# Page07_CPU_PHY.net
KiCad netlist of a schematic drawn in Altium Designer
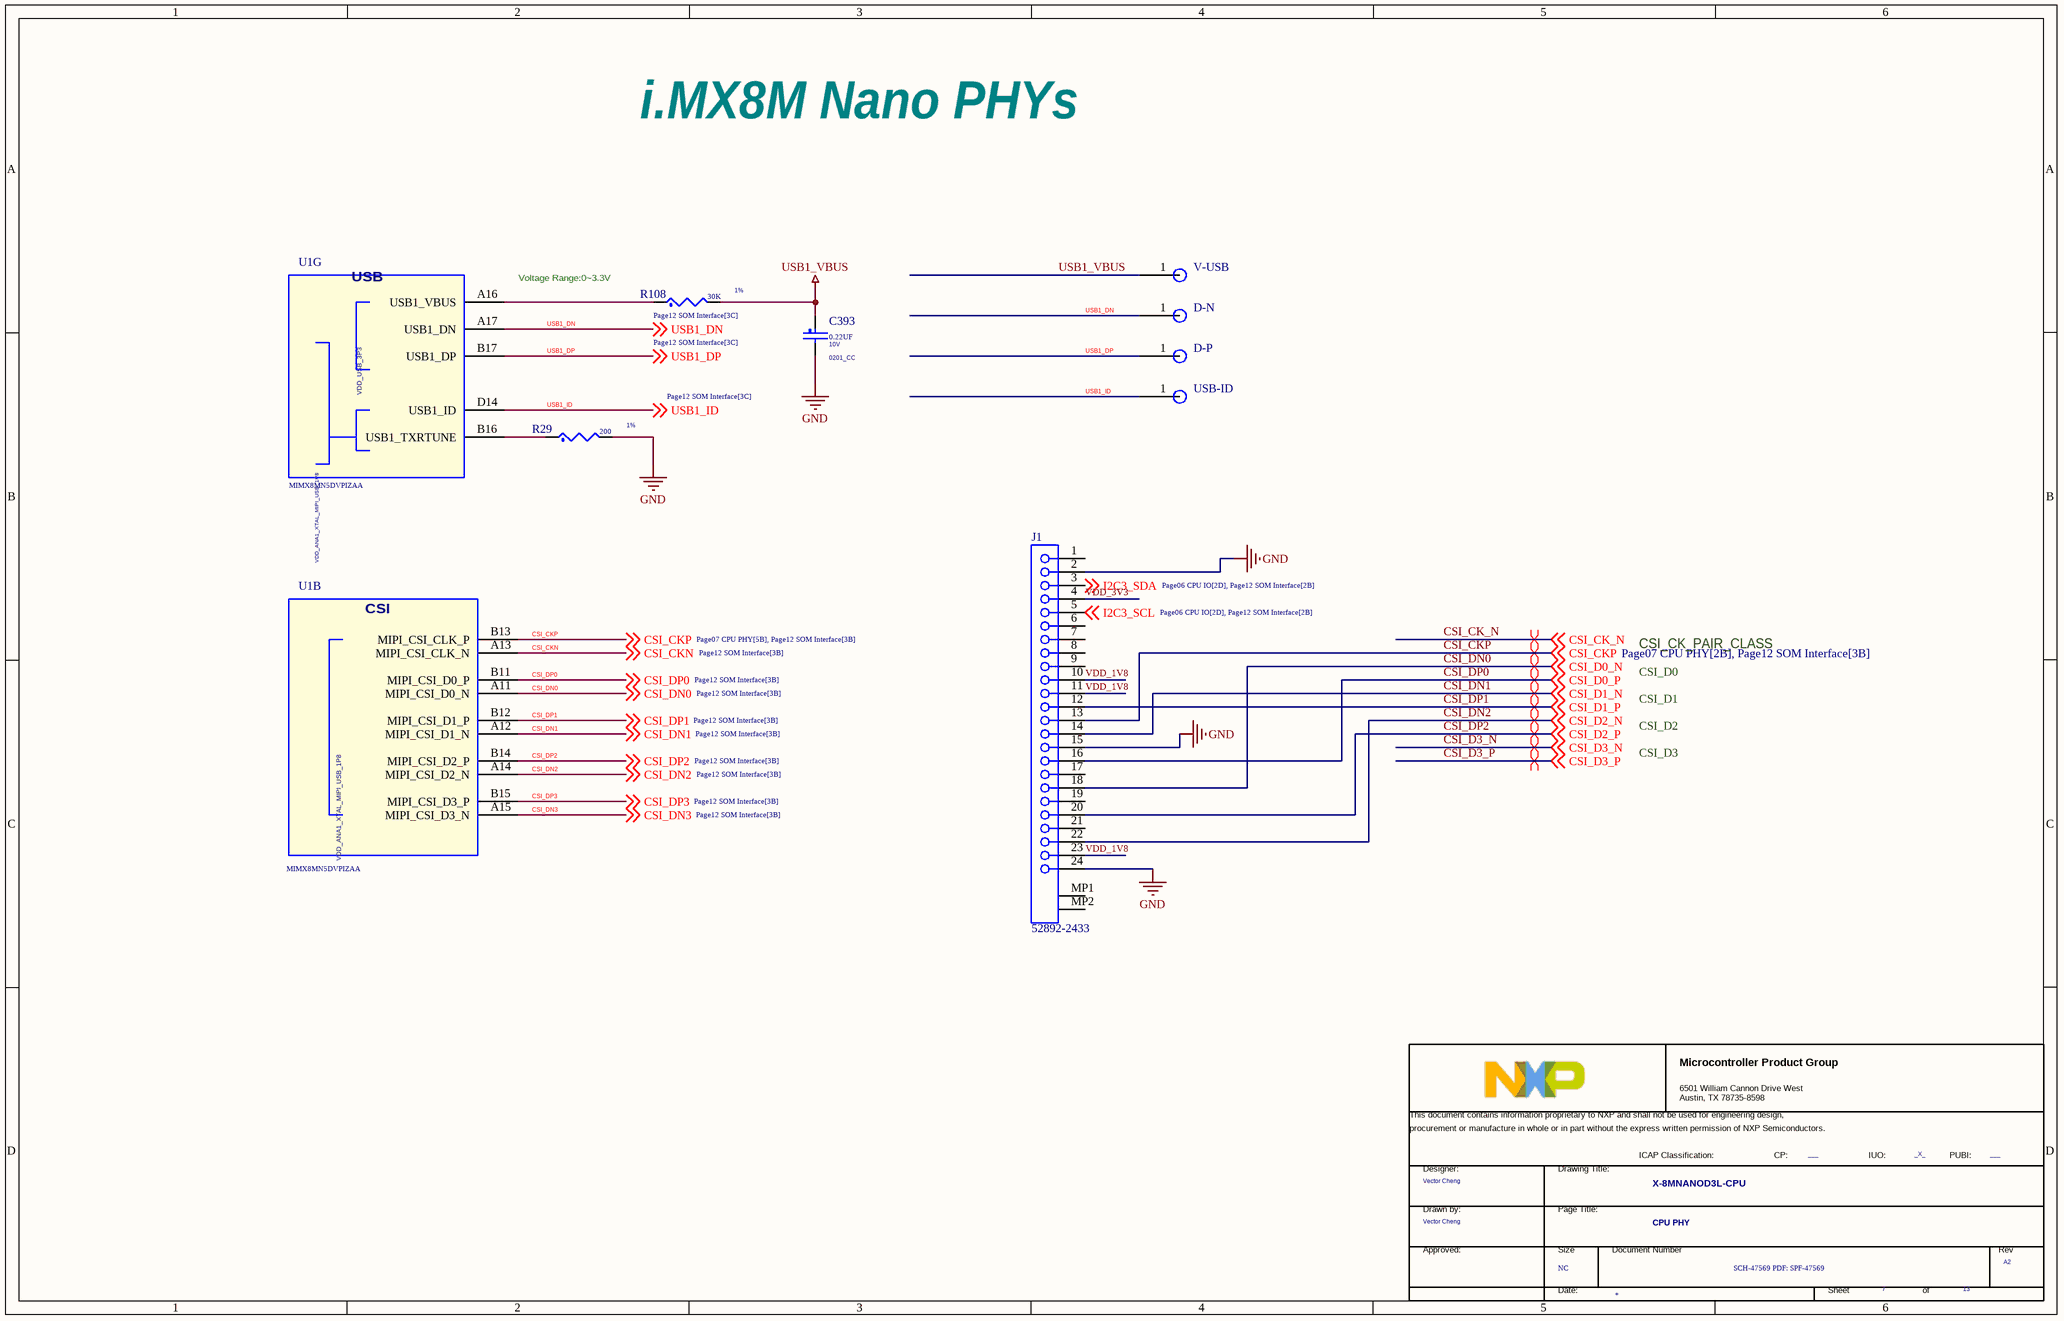
[diagram p0: Page07 CPU PHY.SchDoc]

(export (version "E")
  (design (tool "Eeschema 10.0.6"))
  (components
    (comp (ref "*")
      (value "TitleBlock_MCPG")
      (fields
        (field (name "FCP") "___")
        (field (name "FIUO") "_X_")
        (field (name "PUBI") "___")
        (field (name "DRAWNBY") "Vector Cheng")
        (field (name "DESIGNER") "Vector Cheng")
        (field (name "PAGETITLE") "CPU PHY")
        (field (name "PAGE COUNT") "13")
        (field (name "PAGE NUMBER") "7")
        (field (name "PAGE SIZE") "NC")
        (field (name "TITLE") "X-8MNANOD3L-CPU")
        (field (name "REVCODE") "A2")
        (field (name "DOC") "SCH-47569 PDF: SPF-47569")
      )
      (libsource (lib "*") (part "TitleBlock_MCPG"))
    )
    (comp (ref "C393")
      (value "0.22UF")
      (footprint "0201_CC - C")
      (description "CAP CER 0.22UF 10V 20% X5R 0201")
      (fields
        (field (name "VOLTAGE") "10V")
        (field (name "TOLERANCE") "20%")
        (field (name "PCB FOOTPRINT") "0201_CC")
      )
      (libsource (lib "*") (part "CAP_NP"))
    )
    (comp (ref "D-N")
      (value "Test Pin1")
      (footprint "Test Pin")
      (libsource (lib "Altium starter project NANO") (part "Test Pin1"))
    )
    (comp (ref "D-P")
      (value "Test Pin1")
      (footprint "Test Pin")
      (libsource (lib "Altium starter project NANO") (part "Test Pin1"))
    )
    (comp (ref "J1")
      (value "52892-2433")
      (footprint "MOLX-52892-2433")
      (fields (field (name "MANUFACTURER") "Molex"))
      (libsource (lib "Altium Content Vault") (part "MOLX-52892-2433"))
    )
    (comp (ref "R29")
      (value "200")
      (footprint "0201_RES")
      (description "RES MF 200 OHM 1/20W 1% 0201")
      (fields (field (name "TOLERANCE") "1%") (field (name "VOLTAGE") "25V"))
      (libsource (lib "*") (part "RES"))
    )
    (comp (ref "R108")
      (value "30K")
      (footprint "0201_RES")
      (description "RES MF 30K 1/20W 1% 0201")
      (fields (field (name "VOLTAGE") "25V") (field (name "TOLERANCE") "1%"))
      (libsource (lib "*") (part "RES"))
    )
    (comp (ref "U1")
      (value "MIMX8MN5DVPIZAA")
      (footprint "BGA306C50P21X21_1100X1100X101")
      (description "IC CPU QUAD CORTEX A53+M7 1.4GHZ -- BGA306")
      (libsource (lib "*") (part "MIMX8MN"))
    )
    (comp (ref "USB-ID")
      (value "Test Pin1")
      (footprint "Test Pin")
      (libsource (lib "Altium starter project NANO") (part "Test Pin1"))
    )
    (comp (ref "V-USB")
      (value "Test Pin1")
      (footprint "Test Pin")
      (libsource (lib "Altium starter project NANO") (part "Test Pin1"))
    )
  )
  (nets
    (net (code "1") (name "/VDD_1V8") (class "Default")
      (node (ref "J1") (pin "10") (pinfunction "10_10") (pintype "passive"))
      (node (ref "J1") (pin "11") (pinfunction "11_11") (pintype "passive"))
      (node (ref "J1") (pin "23") (pinfunction "23_23") (pintype "passive"))
    )
    (net (code "2") (name "/VDD_3V3") (class "Default")
      (node (ref "J1") (pin "4") (pinfunction "4_4") (pintype "passive"))
    )
    (net (code "3") (name "CSI_CKN") (class "Default")
      (node (ref "U1") (pin "A13") (pinfunction "MIPI_CSI_CLK_N_A13") (pintype "passive"))
    )
    (net (code "4") (name "CSI_CKP") (class "Default")
      (node (ref "J1") (pin "13") (pinfunction "13_13") (pintype "passive"))
      (node (ref "U1") (pin "B13") (pinfunction "MIPI_CSI_CLK_P_B13") (pintype "passive"))
    )
    (net (code "6") (name "CSI_D0_N") (class "Default")
      (node (ref "J1") (pin "18") (pinfunction "18_18") (pintype "passive"))
      (node (ref "U1") (pin "A11") (pinfunction "MIPI_CSI_D0_N_A11") (pintype "passive"))
    )
    (net (code "7") (name "CSI_D0_P") (class "Default")
      (node (ref "J1") (pin "16") (pinfunction "16_16") (pintype "passive"))
      (node (ref "U1") (pin "B11") (pinfunction "MIPI_CSI_D0_P_B11") (pintype "passive"))
    )
    (net (code "8") (name "CSI_D1_N") (class "Default")
      (node (ref "J1") (pin "14") (pinfunction "14_14") (pintype "passive"))
      (node (ref "U1") (pin "A12") (pinfunction "MIPI_CSI_D1_N_A12") (pintype "passive"))
    )
    (net (code "9") (name "CSI_D1_P") (class "Default")
      (node (ref "J1") (pin "12") (pinfunction "12_12") (pintype "passive"))
      (node (ref "U1") (pin "B12") (pinfunction "MIPI_CSI_D1_P_B12") (pintype "passive"))
    )
    (net (code "10") (name "CSI_D2_N") (class "Default")
      (node (ref "J1") (pin "22") (pinfunction "22_22") (pintype "passive"))
      (node (ref "U1") (pin "A14") (pinfunction "MIPI_CSI_D2_N_A14") (pintype "passive"))
    )
    (net (code "11") (name "CSI_D2_P") (class "Default")
      (node (ref "J1") (pin "20") (pinfunction "20_20") (pintype "passive"))
      (node (ref "U1") (pin "B14") (pinfunction "MIPI_CSI_D2_P_B14") (pintype "passive"))
    )
    (net (code "14") (name "CSI_DN3") (class "Default")
      (node (ref "U1") (pin "A15") (pinfunction "MIPI_CSI_D3_N_A15") (pintype "passive"))
    )
    (net (code "15") (name "CSI_DP3") (class "Default")
      (node (ref "U1") (pin "B15") (pinfunction "MIPI_CSI_D3_P_B15") (pintype "passive"))
    )
    (net (code "16") (name "GND") (class "Default")
      (node (ref "C393") (pin "2") (pinfunction "2_2") (pintype "passive"))
      (node (ref "J1") (pin "15") (pinfunction "15_15") (pintype "passive"))
      (node (ref "J1") (pin "2") (pinfunction "2_2") (pintype "passive"))
      (node (ref "J1") (pin "24") (pinfunction "24_24") (pintype "passive"))
      (node (ref "R29") (pin "2") (pinfunction "2_2") (pintype "passive"))
    )
    (net (code "17") (name "I2C3_SCL") (class "Default")
      (node (ref "J1") (pin "5") (pinfunction "5_5") (pintype "passive"))
    )
    (net (code "18") (name "I2C3_SDA") (class "Default")
      (node (ref "J1") (pin "3") (pinfunction "3_3") (pintype "passive"))
    )
    (net (code "19") (name "Net-(U1G-USB1_TXRTUNE)") (class "Default")
      (node (ref "R29") (pin "1") (pinfunction "1_1") (pintype "passive"))
      (node (ref "U1") (pin "B16") (pinfunction "USB1_TXRTUNE_B16") (pintype "passive"))
    )
    (net (code "20") (name "Net-(U1G-USB1_VBUS)") (class "Default")
      (node (ref "R108") (pin "1") (pinfunction "1_1") (pintype "passive"))
      (node (ref "U1") (pin "A16") (pinfunction "USB1_VBUS_A16") (pintype "passive"))
    )
    (net (code "21") (name "USB1_DN") (class "Default")
      (node (ref "D-N") (pin "1") (pinfunction "1_1") (pintype "passive"))
      (node (ref "U1") (pin "A17") (pinfunction "USB1_DN_A17") (pintype "passive"))
    )
    (net (code "22") (name "USB1_DP") (class "Default")
      (node (ref "D-P") (pin "1") (pinfunction "1_1") (pintype "passive"))
      (node (ref "U1") (pin "B17") (pinfunction "USB1_DP_B17") (pintype "passive"))
    )
    (net (code "23") (name "USB1_ID") (class "Default")
      (node (ref "U1") (pin "D14") (pinfunction "USB1_ID_D14") (pintype "passive"))
      (node (ref "USB-ID") (pin "1") (pinfunction "1_1") (pintype "passive"))
    )
    (net (code "24") (name "USB1_VBUS") (class "Default")
      (node (ref "C393") (pin "1") (pinfunction "1_1") (pintype "passive"))
      (node (ref "R108") (pin "2") (pinfunction "2_2") (pintype "passive"))
      (node (ref "V-USB") (pin "1") (pinfunction "1_1") (pintype "passive"))
    )
    (net (code "25") (name "unconnected-(J1-Pad1)") (class "Default")
      (node (ref "J1") (pin "1") (pinfunction "1_1") (pintype "passive"))
    )
    (net (code "26") (name "unconnected-(J1-Pad6)") (class "Default")
      (node (ref "J1") (pin "6") (pinfunction "6_6") (pintype "passive"))
    )
    (net (code "27") (name "unconnected-(J1-Pad7)") (class "Default")
      (node (ref "J1") (pin "7") (pinfunction "7_7") (pintype "passive"))
    )
    (net (code "28") (name "unconnected-(J1-Pad8)") (class "Default")
      (node (ref "J1") (pin "8") (pinfunction "8_8") (pintype "passive"))
    )
    (net (code "29") (name "unconnected-(J1-Pad9)") (class "Default")
      (node (ref "J1") (pin "9") (pinfunction "9_9") (pintype "passive"))
    )
    (net (code "30") (name "unconnected-(J1-Pad17)") (class "Default")
      (node (ref "J1") (pin "17") (pinfunction "17_17") (pintype "passive"))
    )
    (net (code "31") (name "unconnected-(J1-Pad19)") (class "Default")
      (node (ref "J1") (pin "19") (pinfunction "19_19") (pintype "passive"))
    )
    (net (code "32") (name "unconnected-(J1-Pad21)") (class "Default")
      (node (ref "J1") (pin "21") (pinfunction "21_21") (pintype "passive"))
    )
    (net (code "33") (name "unconnected-(J1-PadMP1)") (class "Default")
      (node (ref "J1") (pin "MP1") (pinfunction "MP1_MP1") (pintype "passive"))
    )
    (net (code "34") (name "unconnected-(J1-PadMP2)") (class "Default")
      (node (ref "J1") (pin "MP2") (pinfunction "MP2_MP2") (pintype "passive"))
    )
  )
)
